# thole_jst_test.net
KiCad netlist of a schematic drawn in EAGLE
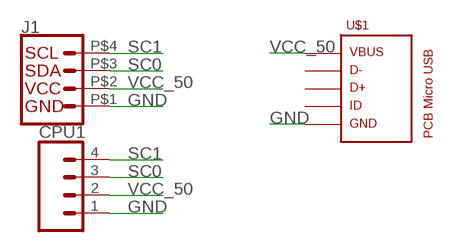
[diagram p0: schematic, sheet 1]

(export (version "E")
  (design (tool "Eeschema 10.0.6"))
  (components
    (comp (ref "CPU1")
      (value "CONN_041X04_NO_SILK")
      (footprint "eagle-import:1X04_NO_SILK")
      (libsource (lib "eagle-import") (part "CONN_041X04_NO_SILK"))
    )
    (comp (ref "J1")
      (value "Vertical Qwiic Connector")
      (footprint "eagle-import:JST04_1MM_HOLES")
      (libsource (lib "eagle-import") (part "QWIIC_CONNECTORJST04_1MM_HOLE"))
    )
    (comp (ref "U$1")
      (value "PCB_MICRO_USB_BSS_2")
      (footprint "eagle-import:USB_TYPE_B_SS_2")
      (libsource (lib "eagle-import") (part "PCB_MICRO_USB_BSS_2"))
    )
  )
  (nets
    (net (code "1") (name "/GND") (class "Default")
      (node (ref "CPU1") (pin "1") (pinfunction "1_1") (pintype "passive"))
      (node (ref "J1") (pin "P$1") (pinfunction "1_P$1") (pintype "power_in"))
      (node (ref "U$1") (pin "5") (pinfunction "5_5") (pintype "bidirectional"))
    )
    (net (code "2") (name "/SC0") (class "Default")
      (node (ref "CPU1") (pin "3") (pinfunction "3_3") (pintype "passive"))
      (node (ref "J1") (pin "P$3") (pinfunction "3_P$3") (pintype "passive"))
    )
    (net (code "3") (name "/SC1") (class "Default")
      (node (ref "CPU1") (pin "4") (pinfunction "4_4") (pintype "passive"))
      (node (ref "J1") (pin "P$4") (pinfunction "4_P$4") (pintype "passive"))
    )
    (net (code "4") (name "/VCC_50") (class "Default")
      (node (ref "CPU1") (pin "2") (pinfunction "2_2") (pintype "passive"))
      (node (ref "J1") (pin "P$2") (pinfunction "2_P$2") (pintype "power_in"))
      (node (ref "U$1") (pin "1") (pinfunction "1_1") (pintype "bidirectional"))
    )
    (net (code "5") (name "unconnected-(U$1-Pad2)") (class "Default")
      (node (ref "U$1") (pin "2") (pinfunction "2_2") (pintype "bidirectional"))
    )
    (net (code "6") (name "unconnected-(U$1-Pad3)") (class "Default")
      (node (ref "U$1") (pin "3") (pinfunction "3_3") (pintype "bidirectional"))
    )
    (net (code "7") (name "unconnected-(U$1-Pad4)") (class "Default")
      (node (ref "U$1") (pin "4") (pinfunction "4_4") (pintype "bidirectional"))
    )
  )
)
